# Dual_Power.net
KiCad netlist of a schematic drawn in EAGLE
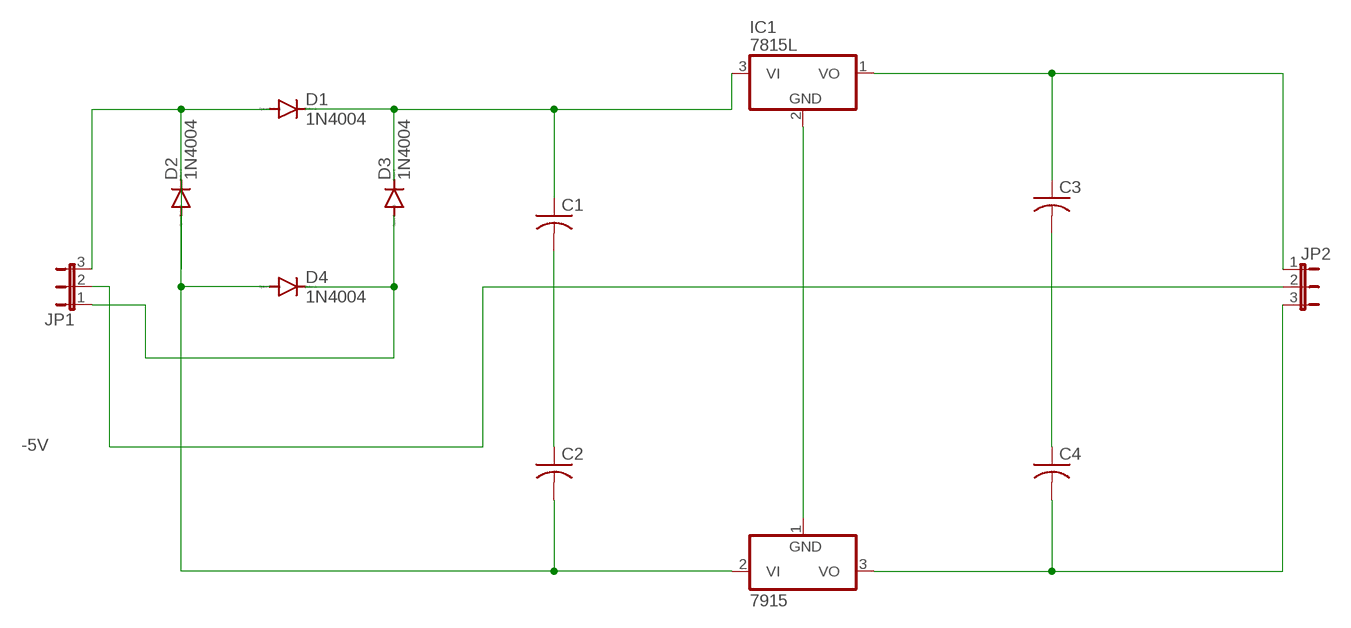
[diagram p0: schematic, sheet 1]

(export (version "E")
  (design (tool "Eeschema 10.0.6"))
  (components
    (comp (ref "7915")
      (value "7915L")
      (footprint "eagle-import:TO92")
      (libsource (lib "eagle-import") (part "79L15"))
    )
    (comp (ref "C1")
      (value "C-US025-025X050")
      (footprint "eagle-import:C025-025X050")
      (libsource (lib "eagle-import") (part "C-US025-025X050"))
    )
    (comp (ref "C2")
      (value "C-US025-025X050")
      (footprint "eagle-import:C025-025X050")
      (libsource (lib "eagle-import") (part "C-US025-025X050"))
    )
    (comp (ref "C3")
      (value "C-US025-025X050")
      (footprint "eagle-import:C025-025X050")
      (libsource (lib "eagle-import") (part "C-US025-025X050"))
    )
    (comp (ref "C4")
      (value "C-US025-025X050")
      (footprint "eagle-import:C025-025X050")
      (libsource (lib "eagle-import") (part "C-US025-025X050"))
    )
    (comp (ref "D1")
      (value "1N4004")
      (footprint "eagle-import:DO41-10")
      (libsource (lib "eagle-import") (part "1N4004"))
    )
    (comp (ref "D2")
      (value "1N4004")
      (footprint "eagle-import:DO41-10")
      (libsource (lib "eagle-import") (part "1N4004"))
    )
    (comp (ref "D3")
      (value "1N4004")
      (footprint "eagle-import:DO41-10")
      (libsource (lib "eagle-import") (part "1N4004"))
    )
    (comp (ref "D4")
      (value "1N4004")
      (footprint "eagle-import:DO41-10")
      (libsource (lib "eagle-import") (part "1N4004"))
    )
    (comp (ref "IC1")
      (value "7815L")
      (footprint "eagle-import:TO92")
      (libsource (lib "eagle-import") (part "78L15"))
    )
    (comp (ref "JP1")
      (value "JP2E")
      (footprint "eagle-import:JP2")
      (libsource (lib "eagle-import") (part "JP2E"))
    )
    (comp (ref "JP2")
      (value "-5V")
      (footprint "eagle-import:JP2")
      (libsource (lib "eagle-import") (part "JP2E"))
    )
  )
  (nets
    (net (code "1") (name "Net-(7915-GND)") (class "Default")
      (node (ref "7915") (pin "1") (pinfunction "GND_1") (pintype "passive"))
      (node (ref "IC1") (pin "2") (pinfunction "GND_2") (pintype "passive"))
    )
    (net (code "2") (name "Net-(7915-VI)") (class "Default")
      (node (ref "7915") (pin "2") (pinfunction "VI_2") (pintype "input"))
      (node (ref "C2") (pin "2") (pinfunction "2_2") (pintype "passive"))
      (node (ref "D2") (pin "A") (pinfunction "A_A") (pintype "passive"))
      (node (ref "D4") (pin "A") (pinfunction "A_A") (pintype "passive"))
    )
    (net (code "3") (name "Net-(7915-VO)") (class "Default")
      (node (ref "7915") (pin "3") (pinfunction "VO_3") (pintype "passive"))
      (node (ref "C4") (pin "2") (pinfunction "2_2") (pintype "passive"))
      (node (ref "JP2") (pin "3") (pinfunction "3_3") (pintype "passive"))
    )
    (net (code "4") (name "Net-(C1-Pad2)") (class "Default")
      (node (ref "C1") (pin "2") (pinfunction "2_2") (pintype "passive"))
      (node (ref "C2") (pin "1") (pinfunction "1_1") (pintype "passive"))
    )
    (net (code "5") (name "Net-(C3-Pad2)") (class "Default")
      (node (ref "C3") (pin "2") (pinfunction "2_2") (pintype "passive"))
      (node (ref "C4") (pin "1") (pinfunction "1_1") (pintype "passive"))
    )
    (net (code "6") (name "Net-(D1-PadA)") (class "Default")
      (node (ref "D1") (pin "A") (pinfunction "A_A") (pintype "passive"))
      (node (ref "D2") (pin "C") (pinfunction "C_C") (pintype "passive"))
      (node (ref "JP1") (pin "3") (pinfunction "3_3") (pintype "passive"))
    )
    (net (code "7") (name "Net-(D3-PadA)") (class "Default")
      (node (ref "D3") (pin "A") (pinfunction "A_A") (pintype "passive"))
      (node (ref "D4") (pin "C") (pinfunction "C_C") (pintype "passive"))
      (node (ref "JP1") (pin "1") (pinfunction "1_1") (pintype "passive"))
    )
    (net (code "8") (name "Net-(IC1-VI)") (class "Default")
      (node (ref "C1") (pin "1") (pinfunction "1_1") (pintype "passive"))
      (node (ref "D1") (pin "C") (pinfunction "C_C") (pintype "passive"))
      (node (ref "D3") (pin "C") (pinfunction "C_C") (pintype "passive"))
      (node (ref "IC1") (pin "3") (pinfunction "VI_3") (pintype "input"))
    )
    (net (code "9") (name "Net-(IC1-VO)") (class "Default")
      (node (ref "C3") (pin "1") (pinfunction "1_1") (pintype "passive"))
      (node (ref "IC1") (pin "1") (pinfunction "VO_1") (pintype "passive"))
      (node (ref "JP2") (pin "1") (pinfunction "1_1") (pintype "passive"))
    )
    (net (code "10") (name "Net-(JP1-Pad2)") (class "Default")
      (node (ref "JP1") (pin "2") (pinfunction "2_2") (pintype "passive"))
      (node (ref "JP2") (pin "2") (pinfunction "2_2") (pintype "passive"))
    )
  )
)
